# TMC2130.net
KiCad netlist of a schematic drawn in Altium Designer
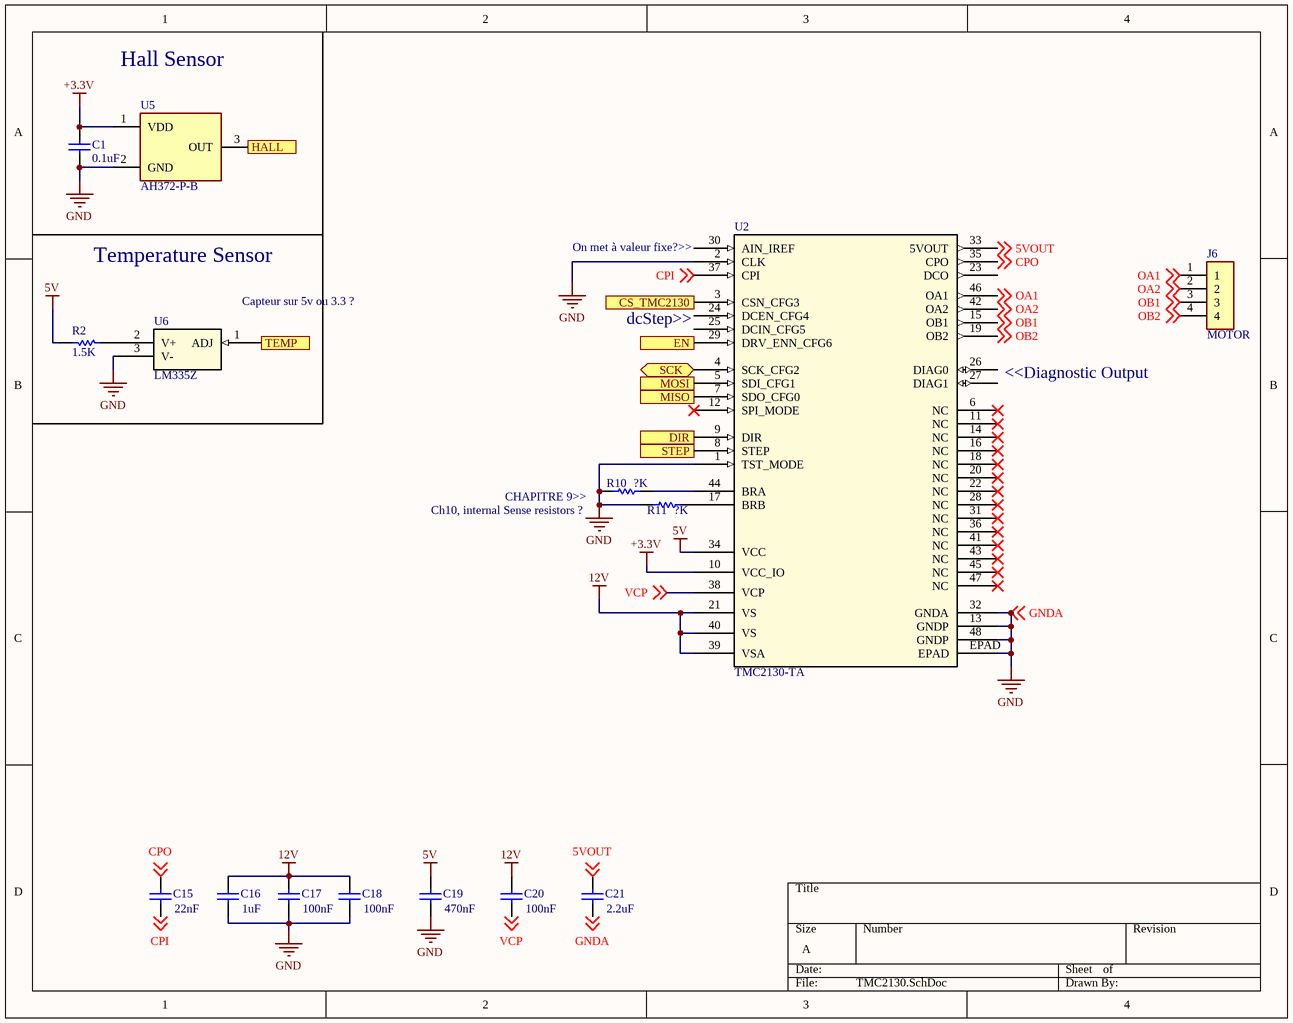
[diagram p0: TMC2130.SchDoc]

(export (version "E")
  (design (tool "Eeschema 10.0.6"))
  (components
    (comp (ref "C1")
      (value "0.1uF")
      (footprint "RAD-0.3")
      (description "Capacitor")
      (fields (field (name "PUBLISHER") "Altium Limited"))
      (libsource (lib "Miscellaneous Devices") (part "Cap"))
    )
    (comp (ref "C15")
      (value "22nF")
      (footprint "RAD-0.3")
      (description "Capacitor")
      (fields (field (name "Comment") "Cap") (field (name "PUBLISHER") "Altium Limited"))
      (libsource (lib "Miscellaneous Devices") (part "Cap"))
    )
    (comp (ref "C16")
      (value "1uF")
      (footprint "RAD-0.3")
      (description "Capacitor")
      (fields (field (name "Comment") "Cap") (field (name "PUBLISHER") "Altium Limited"))
      (libsource (lib "Miscellaneous Devices") (part "Cap"))
    )
    (comp (ref "C17")
      (value "100nF")
      (footprint "RAD-0.3")
      (description "Capacitor")
      (fields (field (name "Comment") "Cap") (field (name "PUBLISHER") "Altium Limited"))
      (libsource (lib "Miscellaneous Devices") (part "Cap"))
    )
    (comp (ref "C18")
      (value "100nF")
      (footprint "RAD-0.3")
      (description "Capacitor")
      (fields (field (name "Comment") "Cap") (field (name "PUBLISHER") "Altium Limited"))
      (libsource (lib "Miscellaneous Devices") (part "Cap"))
    )
    (comp (ref "C19")
      (value "470nF")
      (footprint "RAD-0.3")
      (description "Capacitor")
      (fields (field (name "Comment") "Cap") (field (name "PUBLISHER") "Altium Limited"))
      (libsource (lib "Miscellaneous Devices") (part "Cap"))
    )
    (comp (ref "C20")
      (value "100nF")
      (footprint "RAD-0.3")
      (description "Capacitor")
      (fields (field (name "Comment") "Cap") (field (name "PUBLISHER") "Altium Limited"))
      (libsource (lib "Miscellaneous Devices") (part "Cap"))
    )
    (comp (ref "C21")
      (value "2.2uF")
      (footprint "RAD-0.3")
      (description "Capacitor")
      (fields (field (name "Comment") "Cap") (field (name "PUBLISHER") "Altium Limited"))
      (libsource (lib "Miscellaneous Devices") (part "Cap"))
    )
    (comp (ref "J6")
      (value "MOTOR")
      (footprint "Footprint_Emile:SHDR4W64P0X250_1X4_1240X1155X700P")
      (description "Connector")
      (fields
        (field (name "MANUFACTURER_PART_NUMBER") "S4B-XH-A(LF)(SN)")
        (field (name "RS PART NUMBER") "8201589P")
      )
      (libsource (lib "Schematic_Emile") (part "JST 4POS"))
    )
    (comp (ref "R2")
      (value "1.5K")
      (footprint "AXIAL-0.3")
      (description "Resistor")
      (fields (field (name "PUBLISHER") "Altium Limited"))
      (libsource (lib "Miscellaneous Devices") (part "Res1"))
    )
    (comp (ref "R10")
      (value "?K")
      (footprint "AXIAL-0.3")
      (description "Resistor")
      (fields (field (name "Comment") "Res1") (field (name "PUBLISHER") "Altium Limited"))
      (libsource (lib "Miscellaneous Devices") (part "Res1"))
    )
    (comp (ref "R11")
      (value "?K")
      (footprint "AXIAL-0.3")
      (description "Resistor")
      (fields (field (name "Comment") "Res1") (field (name "PUBLISHER") "Altium Limited"))
      (libsource (lib "Miscellaneous Devices") (part "Res1"))
    )
    (comp (ref "U2")
      (value "TMC2130-TA")
      (footprint "eTQFP48_9x9")
      (description "Motor Driver TMC2130")
      (fields (field (name "COPYRIGHT") "Copyright (C) 2016 Accelerated Designs. All rights reserved"))
      (libsource (lib "Schematic_Emile") (part "TMC2130-TA"))
    )
    (comp (ref "U5")
      (value "AH372-P-B")
      (footprint "SamacSys:AH372PB")
      (description "Hall Sensor")
      (fields (field (name "MOUSER PART NUMBER") "621-AH372-P-B") (field (name "RS PART NUMBER") "1333361P"))
      (libsource (lib "Schematic_Emile") (part "AH372-P-B"))
    )
    (comp (ref "U6")
      (value "LM335Z")
      (footprint "TO92")
      (description "Temperature Sensor")
      (fields (field (name "COPYRIGHT") "Copyright (C) 2018 Accelerated Designs. All rights reserved"))
      (libsource (lib "Schematic_Emile") (part "LM335Z"))
    )
  )
  (nets
    (net (code "1") (name "+3.3V") (class "Default")
      (node (ref "C1") (pin "2") (pinfunction "2_2") (pintype "passive"))
      (node (ref "U2") (pin "10") (pinfunction "VCC_IO_10") (pintype "power_in"))
      (node (ref "U5") (pin "1") (pinfunction "VDD_1") (pintype "passive"))
    )
    (net (code "2") (name "/CS_TMC2130") (class "Default")
      (node (ref "U2") (pin "3") (pinfunction "CSN_CFG3_3") (pintype "input"))
    )
    (net (code "3") (name "/DIR") (class "Default")
      (node (ref "U2") (pin "9") (pinfunction "DIR_9") (pintype "input"))
    )
    (net (code "4") (name "/EN") (class "Default")
      (node (ref "U2") (pin "29") (pinfunction "DRV_ENN_CFG6_29") (pintype "input"))
    )
    (net (code "5") (name "/HALL") (class "Default")
      (node (ref "U5") (pin "3") (pinfunction "OUT_3") (pintype "passive"))
    )
    (net (code "6") (name "/MISO") (class "Default")
      (node (ref "U2") (pin "7") (pinfunction "SDO_CFG0_7") (pintype "input"))
    )
    (net (code "7") (name "/MOSI") (class "Default")
      (node (ref "U2") (pin "5") (pinfunction "SDI_CFG1_5") (pintype "input"))
    )
    (net (code "8") (name "/SCK") (class "Default")
      (node (ref "U2") (pin "4") (pinfunction "SCK_CFG2_4") (pintype "input"))
    )
    (net (code "9") (name "/STEP") (class "Default")
      (node (ref "U2") (pin "8") (pinfunction "STEP_8") (pintype "input"))
    )
    (net (code "10") (name "/TEMP") (class "Default")
      (node (ref "U6") (pin "1") (pinfunction "ADJ_1") (pintype "input"))
    )
    (net (code "11") (name "5V") (class "Default")
      (node (ref "C19") (pin "2") (pinfunction "2_2") (pintype "passive"))
      (node (ref "R2") (pin "1") (pinfunction "1_1") (pintype "passive"))
      (node (ref "U2") (pin "34") (pinfunction "VCC_34") (pintype "power_in"))
    )
    (net (code "12") (name "5VOUT") (class "Default")
      (node (ref "C21") (pin "2") (pinfunction "2_2") (pintype "passive"))
      (node (ref "U2") (pin "33") (pinfunction "5VOUT_33") (pintype "output"))
    )
    (net (code "13") (name "12V") (class "Default")
      (node (ref "C16") (pin "2") (pinfunction "2_2") (pintype "passive"))
      (node (ref "C17") (pin "2") (pinfunction "2_2") (pintype "passive"))
      (node (ref "C18") (pin "2") (pinfunction "2_2") (pintype "passive"))
      (node (ref "C20") (pin "2") (pinfunction "2_2") (pintype "passive"))
      (node (ref "U2") (pin "21") (pinfunction "VS_21") (pintype "power_in"))
      (node (ref "U2") (pin "39") (pinfunction "VSA_39") (pintype "power_in"))
      (node (ref "U2") (pin "40") (pinfunction "VS_40") (pintype "power_in"))
    )
    (net (code "14") (name "CPI") (class "Default")
      (node (ref "C15") (pin "1") (pinfunction "1_1") (pintype "passive"))
      (node (ref "U2") (pin "37") (pinfunction "CPI_37") (pintype "input"))
    )
    (net (code "15") (name "CPO") (class "Default")
      (node (ref "C15") (pin "2") (pinfunction "2_2") (pintype "passive"))
      (node (ref "U2") (pin "35") (pinfunction "CPO_35") (pintype "output"))
    )
    (net (code "16") (name "GND") (class "Default")
      (node (ref "C1") (pin "1") (pinfunction "1_1") (pintype "passive"))
      (node (ref "C16") (pin "1") (pinfunction "1_1") (pintype "passive"))
      (node (ref "C17") (pin "1") (pinfunction "1_1") (pintype "passive"))
      (node (ref "C18") (pin "1") (pinfunction "1_1") (pintype "passive"))
      (node (ref "C19") (pin "1") (pinfunction "1_1") (pintype "passive"))
      (node (ref "C21") (pin "1") (pinfunction "1_1") (pintype "passive"))
      (node (ref "R10") (pin "1") (pinfunction "1_1") (pintype "passive"))
      (node (ref "R11") (pin "1") (pinfunction "1_1") (pintype "passive"))
      (node (ref "U2") (pin "1") (pinfunction "TST_MODE_1") (pintype "input"))
      (node (ref "U2") (pin "13") (pinfunction "GNDP_13") (pintype "power_in"))
      (node (ref "U2") (pin "2") (pinfunction "CLK_2") (pintype "input"))
      (node (ref "U2") (pin "32") (pinfunction "GNDA_32") (pintype "power_in"))
      (node (ref "U2") (pin "48") (pinfunction "GNDP_48") (pintype "power_in"))
      (node (ref "U2") (pin "EPAD") (pinfunction "EPAD_EPAD") (pintype "passive"))
      (node (ref "U5") (pin "2") (pinfunction "GND_2") (pintype "passive"))
      (node (ref "U6") (pin "3") (pinfunction "V-_3") (pintype "power_in"))
    )
    (net (code "17") (name "Net-(U2-BRA)") (class "Default")
      (node (ref "R10") (pin "2") (pinfunction "2_2") (pintype "passive"))
      (node (ref "U2") (pin "44") (pinfunction "BRA_44") (pintype "passive"))
    )
    (net (code "18") (name "Net-(U2-BRB)") (class "Default")
      (node (ref "R11") (pin "2") (pinfunction "2_2") (pintype "passive"))
      (node (ref "U2") (pin "17") (pinfunction "BRB_17") (pintype "passive"))
    )
    (net (code "19") (name "Net-(U6-V+)") (class "Default")
      (node (ref "R2") (pin "2") (pinfunction "2_2") (pintype "passive"))
      (node (ref "U6") (pin "2") (pinfunction "V+_2") (pintype "power_in"))
    )
    (net (code "20") (name "OA1") (class "Default")
      (node (ref "J6") (pin "1") (pinfunction "1_1") (pintype "passive"))
      (node (ref "U2") (pin "46") (pinfunction "OA1_46") (pintype "output"))
    )
    (net (code "21") (name "OA2") (class "Default")
      (node (ref "J6") (pin "2") (pinfunction "2_2") (pintype "passive"))
      (node (ref "U2") (pin "42") (pinfunction "OA2_42") (pintype "output"))
    )
    (net (code "22") (name "OB1") (class "Default")
      (node (ref "J6") (pin "3") (pinfunction "3_3") (pintype "passive"))
      (node (ref "U2") (pin "15") (pinfunction "OB1_15") (pintype "output"))
    )
    (net (code "23") (name "OB2") (class "Default")
      (node (ref "J6") (pin "4") (pinfunction "4_4") (pintype "passive"))
      (node (ref "U2") (pin "19") (pinfunction "OB2_19") (pintype "output"))
    )
    (net (code "24") (name "VCP") (class "Default")
      (node (ref "C20") (pin "1") (pinfunction "1_1") (pintype "passive"))
      (node (ref "U2") (pin "38") (pinfunction "VCP_38") (pintype "power_in"))
    )
    (net (code "25") (name "unconnected-(U2-AIN_IREF-Pad30)") (class "Default")
      (node (ref "U2") (pin "30") (pinfunction "AIN_IREF_30") (pintype "input"))
    )
    (net (code "26") (name "unconnected-(U2-DCEN_CFG4-Pad24)") (class "Default")
      (node (ref "U2") (pin "24") (pinfunction "DCEN_CFG4_24") (pintype "input"))
    )
    (net (code "27") (name "unconnected-(U2-DCIN_CFG5-Pad25)") (class "Default")
      (node (ref "U2") (pin "25") (pinfunction "DCIN_CFG5_25") (pintype "input"))
    )
    (net (code "28") (name "unconnected-(U2-DCO-Pad23)") (class "Default")
      (node (ref "U2") (pin "23") (pinfunction "DCO_23") (pintype "output"))
    )
    (net (code "29") (name "unconnected-(U2-DIAG0-Pad26)") (class "Default")
      (node (ref "U2") (pin "26") (pinfunction "DIAG0_26") (pintype "bidirectional"))
    )
    (net (code "30") (name "unconnected-(U2-DIAG1-Pad27)") (class "Default")
      (node (ref "U2") (pin "27") (pinfunction "DIAG1_27") (pintype "bidirectional"))
    )
    (net (code "31") (name "unconnected-(U2-NC-Pad6)") (class "Default")
      (node (ref "U2") (pin "6") (pinfunction "NC_6") (pintype "passive+no_connect"))
    )
    (net (code "32") (name "unconnected-(U2-NC-Pad11)") (class "Default")
      (node (ref "U2") (pin "11") (pinfunction "NC_11") (pintype "passive+no_connect"))
    )
    (net (code "33") (name "unconnected-(U2-NC-Pad14)") (class "Default")
      (node (ref "U2") (pin "14") (pinfunction "NC_14") (pintype "passive+no_connect"))
    )
    (net (code "34") (name "unconnected-(U2-NC-Pad16)") (class "Default")
      (node (ref "U2") (pin "16") (pinfunction "NC_16") (pintype "passive+no_connect"))
    )
    (net (code "35") (name "unconnected-(U2-NC-Pad18)") (class "Default")
      (node (ref "U2") (pin "18") (pinfunction "NC_18") (pintype "passive+no_connect"))
    )
    (net (code "36") (name "unconnected-(U2-NC-Pad20)") (class "Default")
      (node (ref "U2") (pin "20") (pinfunction "NC_20") (pintype "passive+no_connect"))
    )
    (net (code "37") (name "unconnected-(U2-NC-Pad22)") (class "Default")
      (node (ref "U2") (pin "22") (pinfunction "NC_22") (pintype "passive+no_connect"))
    )
    (net (code "38") (name "unconnected-(U2-NC-Pad28)") (class "Default")
      (node (ref "U2") (pin "28") (pinfunction "NC_28") (pintype "passive+no_connect"))
    )
    (net (code "39") (name "unconnected-(U2-NC-Pad31)") (class "Default")
      (node (ref "U2") (pin "31") (pinfunction "NC_31") (pintype "passive+no_connect"))
    )
    (net (code "40") (name "unconnected-(U2-NC-Pad36)") (class "Default")
      (node (ref "U2") (pin "36") (pinfunction "NC_36") (pintype "passive+no_connect"))
    )
    (net (code "41") (name "unconnected-(U2-NC-Pad41)") (class "Default")
      (node (ref "U2") (pin "41") (pinfunction "NC_41") (pintype "passive+no_connect"))
    )
    (net (code "42") (name "unconnected-(U2-NC-Pad43)") (class "Default")
      (node (ref "U2") (pin "43") (pinfunction "NC_43") (pintype "passive+no_connect"))
    )
    (net (code "43") (name "unconnected-(U2-NC-Pad45)") (class "Default")
      (node (ref "U2") (pin "45") (pinfunction "NC_45") (pintype "passive+no_connect"))
    )
    (net (code "44") (name "unconnected-(U2-NC-Pad47)") (class "Default")
      (node (ref "U2") (pin "47") (pinfunction "NC_47") (pintype "passive+no_connect"))
    )
    (net (code "45") (name "unconnected-(U2-SPI_MODE-Pad12)") (class "Default")
      (node (ref "U2") (pin "12") (pinfunction "SPI_MODE_12") (pintype "input+no_connect"))
    )
  )
)
